# G888X.net
KiCad netlist of a schematic drawn in EAGLE
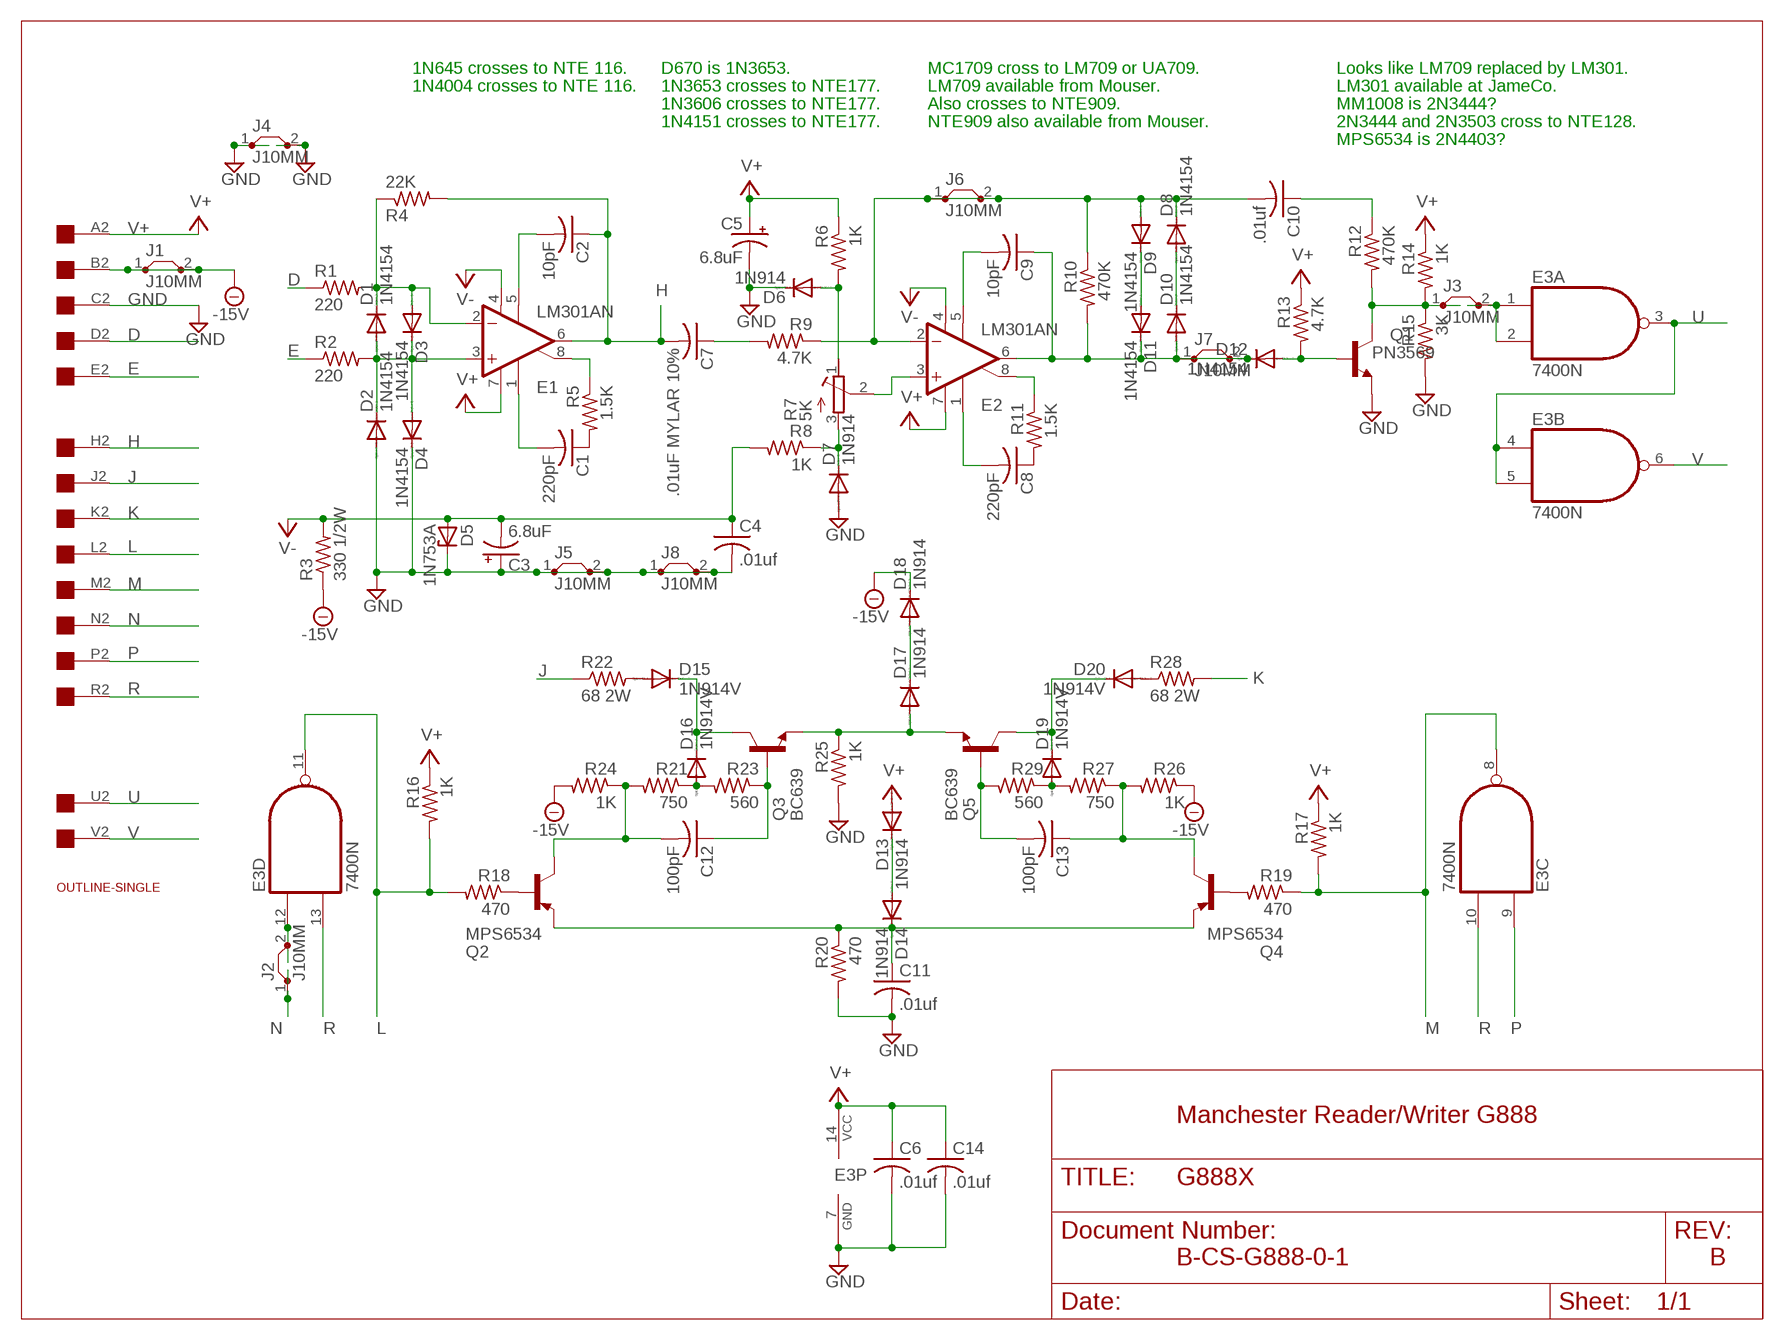
[diagram p0: schematic, sheet 1]

(export (version "E")
  (design (tool "Eeschema 10.0.6"))
  (components
    (comp (ref "C1")
      (value "220pF")
      (footprint "eagle-import:C050-025X075")
      (libsource (lib "eagle-import") (part "C-US050-025X075"))
    )
    (comp (ref "C2")
      (value "10pF")
      (footprint "eagle-import:C050-025X075")
      (libsource (lib "eagle-import") (part "C-US050-025X075"))
    )
    (comp (ref "C3")
      (value "6.8uF")
      (footprint "eagle-import:E12-8")
      (libsource (lib "eagle-import") (part "CPOL-USE20-8AXIAL"))
    )
    (comp (ref "C4")
      (value ".01uf")
      (footprint "eagle-import:C050-025X075")
      (libsource (lib "eagle-import") (part "C-US050-025X075"))
    )
    (comp (ref "C5")
      (value "6.8uF")
      (footprint "eagle-import:E12-8")
      (libsource (lib "eagle-import") (part "CPOL-USE20-8AXIAL"))
    )
    (comp (ref "C6")
      (value ".01uf")
      (footprint "eagle-import:C050-025X075")
      (libsource (lib "eagle-import") (part "C-US050-025X075"))
    )
    (comp (ref "C7")
      (value ".01uF MYLAR 10%")
      (footprint "eagle-import:C225-062X268")
      (libsource (lib "eagle-import") (part "C-US225-062X268"))
    )
    (comp (ref "C8")
      (value "220pF")
      (footprint "eagle-import:C050-025X075")
      (libsource (lib "eagle-import") (part "C-US050-025X075"))
    )
    (comp (ref "C9")
      (value "10pF")
      (footprint "eagle-import:C050-025X075")
      (libsource (lib "eagle-import") (part "C-US050-025X075"))
    )
    (comp (ref "C10")
      (value ".01uf")
      (footprint "eagle-import:C050-025X075")
      (libsource (lib "eagle-import") (part "C-US050-025X075"))
    )
    (comp (ref "C11")
      (value ".01uf")
      (footprint "eagle-import:C050-025X075")
      (libsource (lib "eagle-import") (part "C-US050-025X075"))
    )
    (comp (ref "C12")
      (value "100pF")
      (footprint "eagle-import:C050-025X075")
      (libsource (lib "eagle-import") (part "C-US050-025X075"))
    )
    (comp (ref "C13")
      (value "100pF")
      (footprint "eagle-import:C050-025X075")
      (libsource (lib "eagle-import") (part "C-US050-025X075"))
    )
    (comp (ref "C14")
      (value ".01uf")
      (footprint "eagle-import:C050-025X075")
      (libsource (lib "eagle-import") (part "C-US050-025X075"))
    )
    (comp (ref "D1")
      (value "1N4154")
      (footprint "eagle-import:DO35-10")
      (libsource (lib "eagle-import") (part "DIODE-DO35-10"))
    )
    (comp (ref "D2")
      (value "1N4154")
      (footprint "eagle-import:DO35-10")
      (libsource (lib "eagle-import") (part "DIODE-DO35-10"))
    )
    (comp (ref "D3")
      (value "1N4154")
      (footprint "eagle-import:DO35-10")
      (libsource (lib "eagle-import") (part "DIODE-DO35-10"))
    )
    (comp (ref "D4")
      (value "1N4154")
      (footprint "eagle-import:DO35-10")
      (libsource (lib "eagle-import") (part "DIODE-DO35-10"))
    )
    (comp (ref "D5")
      (value "1N753A")
      (footprint "eagle-import:DO35Z10")
      (libsource (lib "eagle-import") (part "ZENER-DIODEDO35Z10"))
    )
    (comp (ref "D6")
      (value "1N914")
      (footprint "eagle-import:DO35-10")
      (libsource (lib "eagle-import") (part "DIODE-DO35-10"))
    )
    (comp (ref "D7")
      (value "1N914")
      (footprint "eagle-import:DO35-10")
      (libsource (lib "eagle-import") (part "DIODE-DO35-10"))
    )
    (comp (ref "D8")
      (value "1N4154")
      (footprint "eagle-import:DO35-10")
      (libsource (lib "eagle-import") (part "DIODE-DO35-10"))
    )
    (comp (ref "D9")
      (value "1N4154")
      (footprint "eagle-import:DO35-10")
      (libsource (lib "eagle-import") (part "DIODE-DO35-10"))
    )
    (comp (ref "D10")
      (value "1N4154")
      (footprint "eagle-import:DO35-10")
      (libsource (lib "eagle-import") (part "DIODE-DO35-10"))
    )
    (comp (ref "D11")
      (value "1N4154")
      (footprint "eagle-import:DO35-10")
      (libsource (lib "eagle-import") (part "DIODE-DO35-10"))
    )
    (comp (ref "D12")
      (value "1N4154")
      (footprint "eagle-import:DO35-10")
      (libsource (lib "eagle-import") (part "DIODE-DO35-10"))
    )
    (comp (ref "D13")
      (value "1N914")
      (footprint "eagle-import:DO35-10")
      (libsource (lib "eagle-import") (part "DIODE-DO35-10"))
    )
    (comp (ref "D14")
      (value "1N914")
      (footprint "eagle-import:DO35-10")
      (libsource (lib "eagle-import") (part "DIODE-DO35-10"))
    )
    (comp (ref "D15")
      (value "1N914V")
      (footprint "eagle-import:DO35-10")
      (libsource (lib "eagle-import") (part "DIODE-DO35-10"))
    )
    (comp (ref "D16")
      (value "1N914V")
      (footprint "eagle-import:DO35-10")
      (libsource (lib "eagle-import") (part "DIODE-DO35-10"))
    )
    (comp (ref "D17")
      (value "1N914")
      (footprint "eagle-import:DO35-10")
      (libsource (lib "eagle-import") (part "DIODE-DO35-10"))
    )
    (comp (ref "D18")
      (value "1N914")
      (footprint "eagle-import:DO35-10")
      (libsource (lib "eagle-import") (part "DIODE-DO35-10"))
    )
    (comp (ref "D19")
      (value "1N914V")
      (footprint "eagle-import:DO35-10")
      (libsource (lib "eagle-import") (part "DIODE-DO35-10"))
    )
    (comp (ref "D20")
      (value "1N914V")
      (footprint "eagle-import:DO35-10")
      (libsource (lib "eagle-import") (part "DIODE-DO35-10"))
    )
    (comp (ref "E1")
      (value "LM301AN")
      (footprint "eagle-import:DIL08")
      (libsource (lib "eagle-import") (part "MC1709N"))
    )
    (comp (ref "E2")
      (value "LM301AN")
      (footprint "eagle-import:DIL08")
      (libsource (lib "eagle-import") (part "MC1709N"))
    )
    (comp (ref "E3")
      (value "7400N")
      (footprint "eagle-import:DIL14")
      (libsource (lib "eagle-import") (part "7400N"))
    )
    (comp (ref "J1")
      (value "J10MM")
      (footprint "eagle-import:10")
      (libsource (lib "eagle-import") (part "J10MM"))
    )
    (comp (ref "J2")
      (value "J10MM")
      (footprint "eagle-import:10")
      (libsource (lib "eagle-import") (part "J10MM"))
    )
    (comp (ref "J3")
      (value "J10MM")
      (footprint "eagle-import:10")
      (libsource (lib "eagle-import") (part "J10MM"))
    )
    (comp (ref "J4")
      (value "J10MM")
      (footprint "eagle-import:10")
      (libsource (lib "eagle-import") (part "J10MM"))
    )
    (comp (ref "J5")
      (value "J10MM")
      (footprint "eagle-import:10")
      (libsource (lib "eagle-import") (part "J10MM"))
    )
    (comp (ref "J6")
      (value "J10MM")
      (footprint "eagle-import:10")
      (libsource (lib "eagle-import") (part "J10MM"))
    )
    (comp (ref "J7")
      (value "J10MM")
      (footprint "eagle-import:10")
      (libsource (lib "eagle-import") (part "J10MM"))
    )
    (comp (ref "J8")
      (value "J10MM")
      (footprint "eagle-import:10")
      (libsource (lib "eagle-import") (part "J10MM"))
    )
    (comp (ref "Q1")
      (value "PN3569")
      (footprint "eagle-import:TO39")
      (libsource (lib "eagle-import") (part "2N1711"))
    )
    (comp (ref "Q2")
      (value "MPS6534")
      (footprint "eagle-import:TO39")
      (libsource (lib "eagle-import") (part "2N5415"))
    )
    (comp (ref "Q3")
      (value "BC639")
      (footprint "eagle-import:TO39")
      (libsource (lib "eagle-import") (part "2N1711"))
    )
    (comp (ref "Q4")
      (value "MPS6534")
      (footprint "eagle-import:TO39")
      (libsource (lib "eagle-import") (part "2N5415"))
    )
    (comp (ref "Q5")
      (value "BC639")
      (footprint "eagle-import:TO39")
      (libsource (lib "eagle-import") (part "2N1711"))
    )
    (comp (ref "R1")
      (value "220")
      (footprint "eagle-import:0207_10")
      (libsource (lib "eagle-import") (part "R-US_0207/10"))
    )
    (comp (ref "R2")
      (value "220")
      (footprint "eagle-import:0207_10")
      (libsource (lib "eagle-import") (part "R-US_0207/10"))
    )
    (comp (ref "R3")
      (value "330 1/2W")
      (footprint "eagle-import:0411_15")
      (libsource (lib "eagle-import") (part "R-US_0411/15"))
    )
    (comp (ref "R4")
      (value "22K")
      (footprint "eagle-import:0207_10")
      (libsource (lib "eagle-import") (part "R-US_0207/10"))
    )
    (comp (ref "R5")
      (value "1.5K")
      (footprint "eagle-import:0207_10")
      (libsource (lib "eagle-import") (part "R-US_0207/10"))
    )
    (comp (ref "R6")
      (value "1K")
      (footprint "eagle-import:0207_10")
      (libsource (lib "eagle-import") (part "R-US_0207/10"))
    )
    (comp (ref "R7")
      (value "5K")
      (footprint "eagle-import:3006Y")
      (libsource (lib "eagle-import") (part "275P"))
    )
    (comp (ref "R8")
      (value "1K")
      (footprint "eagle-import:0207_10")
      (libsource (lib "eagle-import") (part "R-US_0207/10"))
    )
    (comp (ref "R9")
      (value "4.7K")
      (footprint "eagle-import:0207_10")
      (libsource (lib "eagle-import") (part "R-US_0207/10"))
    )
    (comp (ref "R10")
      (value "470K")
      (footprint "eagle-import:0207_10")
      (libsource (lib "eagle-import") (part "R-US_0207/10"))
    )
    (comp (ref "R11")
      (value "1.5K")
      (footprint "eagle-import:0207_10")
      (libsource (lib "eagle-import") (part "R-US_0207/10"))
    )
    (comp (ref "R12")
      (value "470K")
      (footprint "eagle-import:0207_10")
      (libsource (lib "eagle-import") (part "R-US_0207/10"))
    )
    (comp (ref "R13")
      (value "4.7K")
      (footprint "eagle-import:0207_10")
      (libsource (lib "eagle-import") (part "R-US_0207/10"))
    )
    (comp (ref "R14")
      (value "1K")
      (footprint "eagle-import:0207_10")
      (libsource (lib "eagle-import") (part "R-US_0207/10"))
    )
    (comp (ref "R15")
      (value "3K")
      (footprint "eagle-import:0207_10")
      (libsource (lib "eagle-import") (part "R-US_0207/10"))
    )
    (comp (ref "R16")
      (value "1K")
      (footprint "eagle-import:0207_10")
      (libsource (lib "eagle-import") (part "R-US_0207/10"))
    )
    (comp (ref "R17")
      (value "1K")
      (footprint "eagle-import:0207_10")
      (libsource (lib "eagle-import") (part "R-US_0207/10"))
    )
    (comp (ref "R18")
      (value "470")
      (footprint "eagle-import:0207_10")
      (libsource (lib "eagle-import") (part "R-US_0207/10"))
    )
    (comp (ref "R19")
      (value "470")
      (footprint "eagle-import:0207_10")
      (libsource (lib "eagle-import") (part "R-US_0207/10"))
    )
    (comp (ref "R20")
      (value "470")
      (footprint "eagle-import:0207_10")
      (libsource (lib "eagle-import") (part "R-US_0207/10"))
    )
    (comp (ref "R21")
      (value "750")
      (footprint "eagle-import:0207_10")
      (libsource (lib "eagle-import") (part "R-US_0207/10"))
    )
    (comp (ref "R22")
      (value "68 2W")
      (footprint "eagle-import:P0817_22")
      (libsource (lib "eagle-import") (part "R-US_0817/22"))
    )
    (comp (ref "R23")
      (value "560")
      (footprint "eagle-import:0207_10")
      (libsource (lib "eagle-import") (part "R-US_0207/10"))
    )
    (comp (ref "R24")
      (value "1K")
      (footprint "eagle-import:0207_10")
      (libsource (lib "eagle-import") (part "R-US_0207/10"))
    )
    (comp (ref "R25")
      (value "1K")
      (footprint "eagle-import:0207_10")
      (libsource (lib "eagle-import") (part "R-US_0207/10"))
    )
    (comp (ref "R26")
      (value "1K")
      (footprint "eagle-import:0207_10")
      (libsource (lib "eagle-import") (part "R-US_0207/10"))
    )
    (comp (ref "R27")
      (value "750")
      (footprint "eagle-import:0207_10")
      (libsource (lib "eagle-import") (part "R-US_0207/10"))
    )
    (comp (ref "R28")
      (value "68 2W")
      (footprint "eagle-import:P0817_22")
      (libsource (lib "eagle-import") (part "R-US_0817/22"))
    )
    (comp (ref "R29")
      (value "560")
      (footprint "eagle-import:0207_10")
      (libsource (lib "eagle-import") (part "R-US_0207/10"))
    )
    (comp (ref "U$1")
      (value "EDGE-1")
      (footprint "eagle-import:EDGE-CON1")
      (libsource (lib "eagle-import") (part "EDGE-1"))
    )
    (comp (ref "U$4")
      (value "OUTLINE-SINGLE")
      (footprint "eagle-import:SINGLE")
      (libsource (lib "eagle-import") (part "OUTLINE-SINGLE"))
    )
  )
  (nets
    (net (code "1") (name "-15V") (class "Default")
      (node (ref "D18") (pin "C") (pinfunction "C_C") (pintype "passive"))
      (node (ref "J1") (pin "1") (pinfunction "1_1") (pintype "passive"))
      (node (ref "J1") (pin "2") (pinfunction "2_2") (pintype "passive"))
      (node (ref "R24") (pin "2") (pinfunction "2_2") (pintype "passive"))
      (node (ref "R26") (pin "1") (pinfunction "1_1") (pintype "passive"))
      (node (ref "R3") (pin "1") (pinfunction "1_1") (pintype "passive"))
      (node (ref "U$1") (pin "B2") (pinfunction "1_B2") (pintype "bidirectional"))
    )
    (net (code "2") (name "/D") (class "Default")
      (node (ref "R1") (pin "1") (pinfunction "1_1") (pintype "passive"))
      (node (ref "U$1") (pin "D2") (pinfunction "1_D2") (pintype "bidirectional"))
    )
    (net (code "3") (name "/E") (class "Default")
      (node (ref "R2") (pin "1") (pinfunction "1_1") (pintype "passive"))
      (node (ref "U$1") (pin "E2") (pinfunction "1_E2") (pintype "bidirectional"))
    )
    (net (code "4") (name "/H") (class "Default")
      (node (ref "C2") (pin "1") (pinfunction "1_1") (pintype "passive"))
      (node (ref "C7") (pin "2") (pinfunction "2_2") (pintype "passive"))
      (node (ref "E1") (pin "6") (pinfunction "OUT_6") (pintype "output"))
      (node (ref "R4") (pin "2") (pinfunction "2_2") (pintype "passive"))
      (node (ref "U$1") (pin "H2") (pinfunction "1_H2") (pintype "bidirectional"))
    )
    (net (code "5") (name "/J") (class "Default")
      (node (ref "R22") (pin "1") (pinfunction "1_1") (pintype "passive"))
      (node (ref "U$1") (pin "J2") (pinfunction "1_J2") (pintype "bidirectional"))
    )
    (net (code "6") (name "/K") (class "Default")
      (node (ref "R28") (pin "2") (pinfunction "2_2") (pintype "passive"))
      (node (ref "U$1") (pin "K2") (pinfunction "1_K2") (pintype "bidirectional"))
    )
    (net (code "7") (name "/L") (class "Default")
      (node (ref "E3") (pin "11") (pinfunction "O_11") (pintype "output"))
      (node (ref "R16") (pin "2") (pinfunction "2_2") (pintype "passive"))
      (node (ref "R18") (pin "2") (pinfunction "2_2") (pintype "passive"))
      (node (ref "U$1") (pin "L2") (pinfunction "1_L2") (pintype "bidirectional"))
    )
    (net (code "8") (name "/M") (class "Default")
      (node (ref "E3") (pin "8") (pinfunction "O_8") (pintype "output"))
      (node (ref "R17") (pin "2") (pinfunction "2_2") (pintype "passive"))
      (node (ref "R19") (pin "1") (pinfunction "1_1") (pintype "passive"))
      (node (ref "U$1") (pin "M2") (pinfunction "1_M2") (pintype "bidirectional"))
    )
    (net (code "9") (name "/N") (class "Default")
      (node (ref "E3") (pin "12") (pinfunction "I0_12") (pintype "input"))
      (node (ref "J2") (pin "1") (pinfunction "1_1") (pintype "passive"))
      (node (ref "J2") (pin "2") (pinfunction "2_2") (pintype "passive"))
      (node (ref "U$1") (pin "N2") (pinfunction "1_N2") (pintype "bidirectional"))
    )
    (net (code "10") (name "/P") (class "Default")
      (node (ref "E3") (pin "9") (pinfunction "I0_9") (pintype "input"))
      (node (ref "U$1") (pin "P2") (pinfunction "1_P2") (pintype "bidirectional"))
    )
    (net (code "11") (name "/R") (class "Default")
      (node (ref "E3") (pin "10") (pinfunction "I1_10") (pintype "input"))
      (node (ref "E3") (pin "13") (pinfunction "I1_13") (pintype "input"))
      (node (ref "U$1") (pin "R2") (pinfunction "1_R2") (pintype "bidirectional"))
    )
    (net (code "12") (name "/U") (class "Default")
      (node (ref "E3") (pin "3") (pinfunction "O_3") (pintype "output"))
      (node (ref "E3") (pin "4") (pinfunction "I0_4") (pintype "input"))
      (node (ref "E3") (pin "5") (pinfunction "I1_5") (pintype "input"))
      (node (ref "U$1") (pin "U2") (pinfunction "1_U2") (pintype "bidirectional"))
    )
    (net (code "13") (name "/V") (class "Default")
      (node (ref "E3") (pin "6") (pinfunction "O_6") (pintype "output"))
      (node (ref "U$1") (pin "V2") (pinfunction "1_V2") (pintype "bidirectional"))
    )
    (net (code "14") (name "GND") (class "Default")
      (node (ref "C11") (pin "2") (pinfunction "2_2") (pintype "passive"))
      (node (ref "C14") (pin "2") (pinfunction "2_2") (pintype "passive"))
      (node (ref "C3") (pin "+") (pinfunction "+_+") (pintype "passive"))
      (node (ref "C4") (pin "2") (pinfunction "2_2") (pintype "passive"))
      (node (ref "C5") (pin "-") (pinfunction "-_-") (pintype "passive"))
      (node (ref "C6") (pin "2") (pinfunction "2_2") (pintype "passive"))
      (node (ref "D2") (pin "A") (pinfunction "A_A") (pintype "passive"))
      (node (ref "D4") (pin "C") (pinfunction "C_C") (pintype "passive"))
      (node (ref "D5") (pin "C") (pinfunction "C_C") (pintype "passive"))
      (node (ref "D6") (pin "C") (pinfunction "C_C") (pintype "passive"))
      (node (ref "D7") (pin "A") (pinfunction "A_A") (pintype "passive"))
      (node (ref "E3") (pin "7") (pinfunction "GND_7") (pintype "power_in"))
      (node (ref "J4") (pin "1") (pinfunction "1_1") (pintype "passive"))
      (node (ref "J4") (pin "2") (pinfunction "2_2") (pintype "passive"))
      (node (ref "J5") (pin "1") (pinfunction "1_1") (pintype "passive"))
      (node (ref "J5") (pin "2") (pinfunction "2_2") (pintype "passive"))
      (node (ref "J8") (pin "1") (pinfunction "1_1") (pintype "passive"))
      (node (ref "J8") (pin "2") (pinfunction "2_2") (pintype "passive"))
      (node (ref "Q1") (pin "1") (pinfunction "E_1") (pintype "passive"))
      (node (ref "R15") (pin "2") (pinfunction "2_2") (pintype "passive"))
      (node (ref "R20") (pin "2") (pinfunction "2_2") (pintype "passive"))
      (node (ref "R25") (pin "2") (pinfunction "2_2") (pintype "passive"))
      (node (ref "U$1") (pin "C2") (pinfunction "1_C2") (pintype "bidirectional"))
    )
    (net (code "15") (name "Net-(C1-Pad1)") (class "Default")
      (node (ref "C1") (pin "1") (pinfunction "1_1") (pintype "passive"))
      (node (ref "R5") (pin "2") (pinfunction "2_2") (pintype "passive"))
    )
    (net (code "16") (name "Net-(C7-Pad1)") (class "Default")
      (node (ref "C7") (pin "1") (pinfunction "1_1") (pintype "passive"))
      (node (ref "R9") (pin "2") (pinfunction "2_2") (pintype "passive"))
    )
    (net (code "17") (name "Net-(C8-Pad1)") (class "Default")
      (node (ref "C8") (pin "1") (pinfunction "1_1") (pintype "passive"))
      (node (ref "R11") (pin "2") (pinfunction "2_2") (pintype "passive"))
    )
    (net (code "18") (name "Net-(C10-Pad1)") (class "Default")
      (node (ref "C10") (pin "1") (pinfunction "1_1") (pintype "passive"))
      (node (ref "R12") (pin "1") (pinfunction "1_1") (pintype "passive"))
    )
    (net (code "19") (name "Net-(D10-PadC)") (class "Default")
      (node (ref "D10") (pin "C") (pinfunction "C_C") (pintype "passive"))
      (node (ref "D8") (pin "A") (pinfunction "A_A") (pintype "passive"))
    )
    (net (code "20") (name "Net-(D11-PadA)") (class "Default")
      (node (ref "D11") (pin "A") (pinfunction "A_A") (pintype "passive"))
      (node (ref "D9") (pin "C") (pinfunction "C_C") (pintype "passive"))
    )
    (net (code "21") (name "Net-(D13-PadC)") (class "Default")
      (node (ref "D13") (pin "C") (pinfunction "C_C") (pintype "passive"))
      (node (ref "D14") (pin "A") (pinfunction "A_A") (pintype "passive"))
    )
    (net (code "22") (name "Net-(D15-PadA)") (class "Default")
      (node (ref "D15") (pin "A") (pinfunction "A_A") (pintype "passive"))
      (node (ref "R22") (pin "2") (pinfunction "2_2") (pintype "passive"))
    )
    (net (code "23") (name "Net-(D16-PadA)") (class "Default")
      (node (ref "D16") (pin "A") (pinfunction "A_A") (pintype "passive"))
      (node (ref "R21") (pin "1") (pinfunction "1_1") (pintype "passive"))
      (node (ref "R23") (pin "2") (pinfunction "2_2") (pintype "passive"))
    )
    (net (code "24") (name "Net-(D17-PadC)") (class "Default")
      (node (ref "D17") (pin "C") (pinfunction "C_C") (pintype "passive"))
      (node (ref "D18") (pin "A") (pinfunction "A_A") (pintype "passive"))
    )
    (net (code "25") (name "Net-(D19-PadA)") (class "Default")
      (node (ref "D19") (pin "A") (pinfunction "A_A") (pintype "passive"))
      (node (ref "R27") (pin "2") (pinfunction "2_2") (pintype "passive"))
      (node (ref "R29") (pin "1") (pinfunction "1_1") (pintype "passive"))
    )
    (net (code "26") (name "Net-(D20-PadA)") (class "Default")
      (node (ref "D20") (pin "A") (pinfunction "A_A") (pintype "passive"))
      (node (ref "R28") (pin "1") (pinfunction "1_1") (pintype "passive"))
    )
    (net (code "27") (name "Net-(E1-+IN)") (class "Default")
      (node (ref "D1") (pin "A") (pinfunction "A_A") (pintype "passive"))
      (node (ref "D2") (pin "C") (pinfunction "C_C") (pintype "passive"))
      (node (ref "D3") (pin "C") (pinfunction "C_C") (pintype "passive"))
      (node (ref "D4") (pin "A") (pinfunction "A_A") (pintype "passive"))
      (node (ref "E1") (pin "3") (pinfunction "+IN_3") (pintype "input"))
      (node (ref "R2") (pin "2") (pinfunction "2_2") (pintype "passive"))
    )
    (net (code "28") (name "Net-(E1--IN)") (class "Default")
      (node (ref "D1") (pin "C") (pinfunction "C_C") (pintype "passive"))
      (node (ref "D3") (pin "A") (pinfunction "A_A") (pintype "passive"))
      (node (ref "E1") (pin "2") (pinfunction "-IN_2") (pintype "input"))
      (node (ref "R1") (pin "2") (pinfunction "2_2") (pintype "passive"))
      (node (ref "R4") (pin "1") (pinfunction "1_1") (pintype "passive"))
    )
    (net (code "29") (name "Net-(E1-ON1)") (class "Default")
      (node (ref "C1") (pin "2") (pinfunction "2_2") (pintype "passive"))
      (node (ref "E1") (pin "1") (pinfunction "ON1_1") (pintype "passive"))
    )
    (net (code "30") (name "Net-(E1-ON2)") (class "Default")
      (node (ref "E1") (pin "8") (pinfunction "ON2_8") (pintype "passive"))
      (node (ref "R5") (pin "1") (pinfunction "1_1") (pintype "passive"))
    )
    (net (code "31") (name "Net-(E1-OPT)") (class "Default")
      (node (ref "C2") (pin "2") (pinfunction "2_2") (pintype "passive"))
      (node (ref "E1") (pin "5") (pinfunction "OPT_5") (pintype "passive"))
    )
    (net (code "32") (name "Net-(E2-+IN)") (class "Default")
      (node (ref "E2") (pin "3") (pinfunction "+IN_3") (pintype "input"))
      (node (ref "R7") (pin "2") (pinfunction "S_2") (pintype "passive"))
    )
    (net (code "33") (name "Net-(E2--IN)") (class "Default")
      (node (ref "C10") (pin "2") (pinfunction "2_2") (pintype "passive"))
      (node (ref "D8") (pin "C") (pinfunction "C_C") (pintype "passive"))
      (node (ref "D9") (pin "A") (pinfunction "A_A") (pintype "passive"))
      (node (ref "E2") (pin "2") (pinfunction "-IN_2") (pintype "input"))
      (node (ref "J6") (pin "1") (pinfunction "1_1") (pintype "passive"))
      (node (ref "J6") (pin "2") (pinfunction "2_2") (pintype "passive"))
      (node (ref "R10") (pin "1") (pinfunction "1_1") (pintype "passive"))
      (node (ref "R9") (pin "1") (pinfunction "1_1") (pintype "passive"))
    )
    (net (code "34") (name "Net-(E2-ON1)") (class "Default")
      (node (ref "C8") (pin "2") (pinfunction "2_2") (pintype "passive"))
      (node (ref "E2") (pin "1") (pinfunction "ON1_1") (pintype "passive"))
    )
    (net (code "35") (name "Net-(E2-ON2)") (class "Default")
      (node (ref "E2") (pin "8") (pinfunction "ON2_8") (pintype "passive"))
      (node (ref "R11") (pin "1") (pinfunction "1_1") (pintype "passive"))
    )
    (net (code "36") (name "Net-(E2-OPT)") (class "Default")
      (node (ref "C9") (pin "2") (pinfunction "2_2") (pintype "passive"))
      (node (ref "E2") (pin "5") (pinfunction "OPT_5") (pintype "passive"))
    )
    (net (code "37") (name "Net-(E2-OUT)") (class "Default")
      (node (ref "C9") (pin "1") (pinfunction "1_1") (pintype "passive"))
      (node (ref "D10") (pin "A") (pinfunction "A_A") (pintype "passive"))
      (node (ref "D11") (pin "C") (pinfunction "C_C") (pintype "passive"))
      (node (ref "D12") (pin "C") (pinfunction "C_C") (pintype "passive"))
      (node (ref "E2") (pin "6") (pinfunction "OUT_6") (pintype "output"))
      (node (ref "J7") (pin "1") (pinfunction "1_1") (pintype "passive"))
      (node (ref "J7") (pin "2") (pinfunction "2_2") (pintype "passive"))
      (node (ref "R10") (pin "2") (pinfunction "2_2") (pintype "passive"))
    )
    (net (code "38") (name "Net-(E3A-I0)") (class "Default")
      (node (ref "E3") (pin "1") (pinfunction "I0_1") (pintype "input"))
      (node (ref "E3") (pin "2") (pinfunction "I1_2") (pintype "input"))
      (node (ref "J3") (pin "1") (pinfunction "1_1") (pintype "passive"))
      (node (ref "J3") (pin "2") (pinfunction "2_2") (pintype "passive"))
      (node (ref "Q1") (pin "3") (pinfunction "C_3") (pintype "passive"))
      (node (ref "R12") (pin "2") (pinfunction "2_2") (pintype "passive"))
      (node (ref "R14") (pin "2") (pinfunction "2_2") (pintype "passive"))
      (node (ref "R15") (pin "1") (pinfunction "1_1") (pintype "passive"))
    )
    (net (code "39") (name "Net-(Q1-B)") (class "Default")
      (node (ref "D12") (pin "A") (pinfunction "A_A") (pintype "passive"))
      (node (ref "Q1") (pin "2") (pinfunction "B_2") (pintype "passive"))
      (node (ref "R13") (pin "2") (pinfunction "2_2") (pintype "passive"))
    )
    (net (code "40") (name "Net-(Q2-B)") (class "Default")
      (node (ref "Q2") (pin "2") (pinfunction "B_2") (pintype "passive"))
      (node (ref "R18") (pin "1") (pinfunction "1_1") (pintype "passive"))
    )
    (net (code "41") (name "Net-(Q2-C)") (class "Default")
      (node (ref "C12") (pin "2") (pinfunction "2_2") (pintype "passive"))
      (node (ref "Q2") (pin "3") (pinfunction "C_3") (pintype "passive"))
      (node (ref "R21") (pin "2") (pinfunction "2_2") (pintype "passive"))
      (node (ref "R24") (pin "1") (pinfunction "1_1") (pintype "passive"))
    )
    (net (code "42") (name "Net-(Q2-E)") (class "Default")
      (node (ref "C11") (pin "1") (pinfunction "1_1") (pintype "passive"))
      (node (ref "D14") (pin "C") (pinfunction "C_C") (pintype "passive"))
      (node (ref "Q2") (pin "1") (pinfunction "E_1") (pintype "passive"))
      (node (ref "Q4") (pin "1") (pinfunction "E_1") (pintype "passive"))
      (node (ref "R20") (pin "1") (pinfunction "1_1") (pintype "passive"))
    )
    (net (code "43") (name "Net-(Q3-B)") (class "Default")
      (node (ref "C12") (pin "1") (pinfunction "1_1") (pintype "passive"))
      (node (ref "Q3") (pin "2") (pinfunction "B_2") (pintype "passive"))
      (node (ref "R23") (pin "1") (pinfunction "1_1") (pintype "passive"))
    )
    (net (code "44") (name "Net-(Q3-C)") (class "Default")
      (node (ref "D15") (pin "C") (pinfunction "C_C") (pintype "passive"))
      (node (ref "D16") (pin "C") (pinfunction "C_C") (pintype "passive"))
      (node (ref "Q3") (pin "3") (pinfunction "C_3") (pintype "passive"))
    )
    (net (code "45") (name "Net-(Q3-E)") (class "Default")
      (node (ref "D17") (pin "A") (pinfunction "A_A") (pintype "passive"))
      (node (ref "Q3") (pin "1") (pinfunction "E_1") (pintype "passive"))
      (node (ref "Q5") (pin "1") (pinfunction "E_1") (pintype "passive"))
      (node (ref "R25") (pin "1") (pinfunction "1_1") (pintype "passive"))
    )
    (net (code "46") (name "Net-(Q4-B)") (class "Default")
      (node (ref "Q4") (pin "2") (pinfunction "B_2") (pintype "passive"))
      (node (ref "R19") (pin "2") (pinfunction "2_2") (pintype "passive"))
    )
    (net (code "47") (name "Net-(Q4-C)") (class "Default")
      (node (ref "C13") (pin "1") (pinfunction "1_1") (pintype "passive"))
      (node (ref "Q4") (pin "3") (pinfunction "C_3") (pintype "passive"))
      (node (ref "R26") (pin "2") (pinfunction "2_2") (pintype "passive"))
      (node (ref "R27") (pin "1") (pinfunction "1_1") (pintype "passive"))
    )
    (net (code "48") (name "Net-(Q5-B)") (class "Default")
      (node (ref "C13") (pin "2") (pinfunction "2_2") (pintype "passive"))
      (node (ref "Q5") (pin "2") (pinfunction "B_2") (pintype "passive"))
      (node (ref "R29") (pin "2") (pinfunction "2_2") (pintype "passive"))
    )
    (net (code "49") (name "Net-(Q5-C)") (class "Default")
      (node (ref "D19") (pin "C") (pinfunction "C_C") (pintype "passive"))
      (node (ref "D20") (pin "C") (pinfunction "C_C") (pintype "passive"))
      (node (ref "Q5") (pin "3") (pinfunction "C_3") (pintype "passive"))
    )
    (net (code "50") (name "Net-(R7-A)") (class "Default")
      (node (ref "D6") (pin "A") (pinfunction "A_A") (pintype "passive"))
      (node (ref "R6") (pin "2") (pinfunction "2_2") (pintype "passive"))
      (node (ref "R7") (pin "1") (pinfunction "A_1") (pintype "passive"))
    )
    (net (code "51") (name "Net-(R7-E)") (class "Default")
      (node (ref "D7") (pin "C") (pinfunction "C_C") (pintype "passive"))
      (node (ref "R7") (pin "3") (pinfunction "E_3") (pintype "passive"))
      (node (ref "R8") (pin "1") (pinfunction "1_1") (pintype "passive"))
    )
    (net (code "52") (name "V+") (class "Default")
      (node (ref "C14") (pin "1") (pinfunction "1_1") (pintype "passive"))
      (node (ref "C5") (pin "+") (pinfunction "+_+") (pintype "passive"))
      (node (ref "C6") (pin "1") (pinfunction "1_1") (pintype "passive"))
      (node (ref "D13") (pin "A") (pinfunction "A_A") (pintype "passive"))
      (node (ref "E1") (pin "7") (pinfunction "V+_7") (pintype "power_in"))
      (node (ref "E2") (pin "7") (pinfunction "V+_7") (pintype "power_in"))
      (node (ref "E3") (pin "14") (pinfunction "VCC_14") (pintype "power_in"))
      (node (ref "R13") (pin "1") (pinfunction "1_1") (pintype "passive"))
      (node (ref "R14") (pin "1") (pinfunction "1_1") (pintype "passive"))
      (node (ref "R16") (pin "1") (pinfunction "1_1") (pintype "passive"))
      (node (ref "R17") (pin "1") (pinfunction "1_1") (pintype "passive"))
      (node (ref "R6") (pin "1") (pinfunction "1_1") (pintype "passive"))
      (node (ref "U$1") (pin "A2") (pinfunction "1_A2") (pintype "bidirectional"))
    )
    (net (code "53") (name "V-") (class "Default")
      (node (ref "C3") (pin "-") (pinfunction "-_-") (pintype "passive"))
      (node (ref "C4") (pin "1") (pinfunction "1_1") (pintype "passive"))
      (node (ref "D5") (pin "A") (pinfunction "A_A") (pintype "passive"))
      (node (ref "E1") (pin "4") (pinfunction "V-_4") (pintype "power_in"))
      (node (ref "E2") (pin "4") (pinfunction "V-_4") (pintype "power_in"))
      (node (ref "R3") (pin "2") (pinfunction "2_2") (pintype "passive"))
      (node (ref "R8") (pin "2") (pinfunction "2_2") (pintype "passive"))
    )
  )
)
